# encoder_moduler.net
KiCad netlist of a schematic drawn in EAGLE
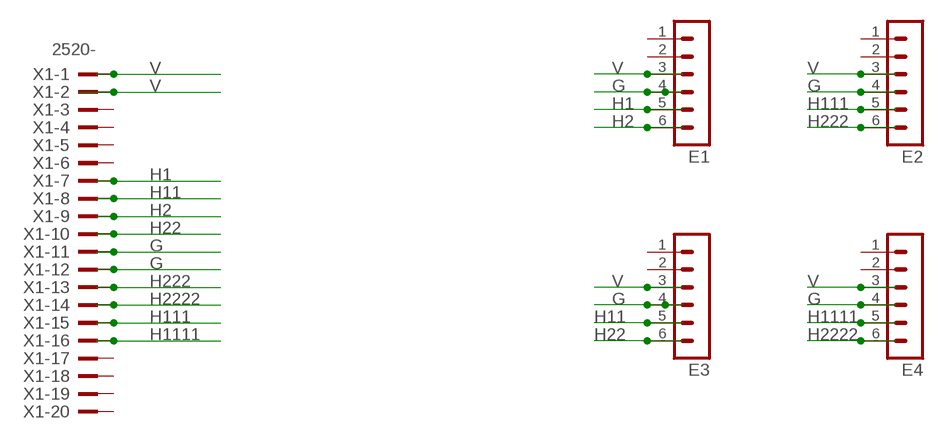
[diagram p0: schematic, sheet 1]

(export (version "E")
  (design (tool "Eeschema 10.0.6"))
  (components
    (comp (ref "E1")
      (value "MA06-1")
      (footprint "eagle-import:MA06-1")
      (libsource (lib "eagle-import") (part "MA06-1"))
    )
    (comp (ref "E2")
      (value "MA06-1")
      (footprint "eagle-import:MA06-1")
      (libsource (lib "eagle-import") (part "MA06-1"))
    )
    (comp (ref "E3")
      (value "MA06-1")
      (footprint "eagle-import:MA06-1")
      (libsource (lib "eagle-import") (part "MA06-1"))
    )
    (comp (ref "E4")
      (value "MA06-1")
      (footprint "eagle-import:MA06-1")
      (libsource (lib "eagle-import") (part "MA06-1"))
    )
    (comp (ref "X1")
      (value "2520-")
      (footprint "eagle-import:PAK100_2500-20")
      (libsource (lib "eagle-import") (part "2520-"))
    )
  )
  (nets
    (net (code "1") (name "/G") (class "Default")
      (node (ref "E1") (pin "4") (pinfunction "4_4") (pintype "passive"))
      (node (ref "E2") (pin "4") (pinfunction "4_4") (pintype "passive"))
      (node (ref "E3") (pin "4") (pinfunction "4_4") (pintype "passive"))
      (node (ref "E4") (pin "4") (pinfunction "4_4") (pintype "passive"))
      (node (ref "X1") (pin "11") (pinfunction "KL_11") (pintype "passive"))
      (node (ref "X1") (pin "12") (pinfunction "KL_12") (pintype "passive"))
    )
    (net (code "2") (name "/H1") (class "Default")
      (node (ref "E1") (pin "5") (pinfunction "5_5") (pintype "passive"))
      (node (ref "X1") (pin "7") (pinfunction "KL_7") (pintype "passive"))
    )
    (net (code "3") (name "/H2") (class "Default")
      (node (ref "E1") (pin "6") (pinfunction "6_6") (pintype "passive"))
      (node (ref "X1") (pin "9") (pinfunction "KL_9") (pintype "passive"))
    )
    (net (code "4") (name "/H11") (class "Default")
      (node (ref "E3") (pin "5") (pinfunction "5_5") (pintype "passive"))
      (node (ref "X1") (pin "8") (pinfunction "KL_8") (pintype "passive"))
    )
    (net (code "5") (name "/H22") (class "Default")
      (node (ref "E3") (pin "6") (pinfunction "6_6") (pintype "passive"))
      (node (ref "X1") (pin "10") (pinfunction "KL_10") (pintype "passive"))
    )
    (net (code "6") (name "/H111") (class "Default")
      (node (ref "E2") (pin "5") (pinfunction "5_5") (pintype "passive"))
      (node (ref "X1") (pin "15") (pinfunction "KL_15") (pintype "passive"))
    )
    (net (code "7") (name "/H222") (class "Default")
      (node (ref "E2") (pin "6") (pinfunction "6_6") (pintype "passive"))
      (node (ref "X1") (pin "13") (pinfunction "KL_13") (pintype "passive"))
    )
    (net (code "8") (name "/H1111") (class "Default")
      (node (ref "E4") (pin "5") (pinfunction "5_5") (pintype "passive"))
      (node (ref "X1") (pin "16") (pinfunction "KL_16") (pintype "passive"))
    )
    (net (code "9") (name "/H2222") (class "Default")
      (node (ref "E4") (pin "6") (pinfunction "6_6") (pintype "passive"))
      (node (ref "X1") (pin "14") (pinfunction "KL_14") (pintype "passive"))
    )
    (net (code "10") (name "/V") (class "Default")
      (node (ref "E1") (pin "3") (pinfunction "3_3") (pintype "passive"))
      (node (ref "E2") (pin "3") (pinfunction "3_3") (pintype "passive"))
      (node (ref "E3") (pin "3") (pinfunction "3_3") (pintype "passive"))
      (node (ref "E4") (pin "3") (pinfunction "3_3") (pintype "passive"))
      (node (ref "X1") (pin "1") (pinfunction "KL_1") (pintype "passive"))
      (node (ref "X1") (pin "2") (pinfunction "KL_2") (pintype "passive"))
    )
    (net (code "11") (name "unconnected-(E1-Pad1)") (class "Default")
      (node (ref "E1") (pin "1") (pinfunction "1_1") (pintype "passive"))
    )
    (net (code "12") (name "unconnected-(E1-Pad2)") (class "Default")
      (node (ref "E1") (pin "2") (pinfunction "2_2") (pintype "passive"))
    )
    (net (code "13") (name "unconnected-(E2-Pad1)") (class "Default")
      (node (ref "E2") (pin "1") (pinfunction "1_1") (pintype "passive"))
    )
    (net (code "14") (name "unconnected-(E2-Pad2)") (class "Default")
      (node (ref "E2") (pin "2") (pinfunction "2_2") (pintype "passive"))
    )
    (net (code "15") (name "unconnected-(E3-Pad1)") (class "Default")
      (node (ref "E3") (pin "1") (pinfunction "1_1") (pintype "passive"))
    )
    (net (code "16") (name "unconnected-(E3-Pad2)") (class "Default")
      (node (ref "E3") (pin "2") (pinfunction "2_2") (pintype "passive"))
    )
    (net (code "17") (name "unconnected-(E4-Pad1)") (class "Default")
      (node (ref "E4") (pin "1") (pinfunction "1_1") (pintype "passive"))
    )
    (net (code "18") (name "unconnected-(E4-Pad2)") (class "Default")
      (node (ref "E4") (pin "2") (pinfunction "2_2") (pintype "passive"))
    )
    (net (code "19") (name "unconnected-(X1I-KL-Pad17)") (class "Default")
      (node (ref "X1") (pin "17") (pinfunction "KL_17") (pintype "passive"))
    )
    (net (code "20") (name "unconnected-(X1J-KL-Pad18)") (class "Default")
      (node (ref "X1") (pin "18") (pinfunction "KL_18") (pintype "passive"))
    )
    (net (code "21") (name "unconnected-(X1K-KL-Pad19)") (class "Default")
      (node (ref "X1") (pin "19") (pinfunction "KL_19") (pintype "passive"))
    )
    (net (code "22") (name "unconnected-(X1M-KL-Pad20)") (class "Default")
      (node (ref "X1") (pin "20") (pinfunction "KL_20") (pintype "passive"))
    )
    (net (code "23") (name "unconnected-(X1N-KL-Pad3)") (class "Default")
      (node (ref "X1") (pin "3") (pinfunction "KL_3") (pintype "passive"))
    )
    (net (code "24") (name "unconnected-(X1O-KL-Pad4)") (class "Default")
      (node (ref "X1") (pin "4") (pinfunction "KL_4") (pintype "passive"))
    )
    (net (code "25") (name "unconnected-(X1P-KL-Pad5)") (class "Default")
      (node (ref "X1") (pin "5") (pinfunction "KL_5") (pintype "passive"))
    )
    (net (code "26") (name "unconnected-(X1Q-KL-Pad6)") (class "Default")
      (node (ref "X1") (pin "6") (pinfunction "KL_6") (pintype "passive"))
    )
  )
)
